# Mako_DSP_USBR1_1.net
KiCad netlist of a schematic drawn in Altium Designer
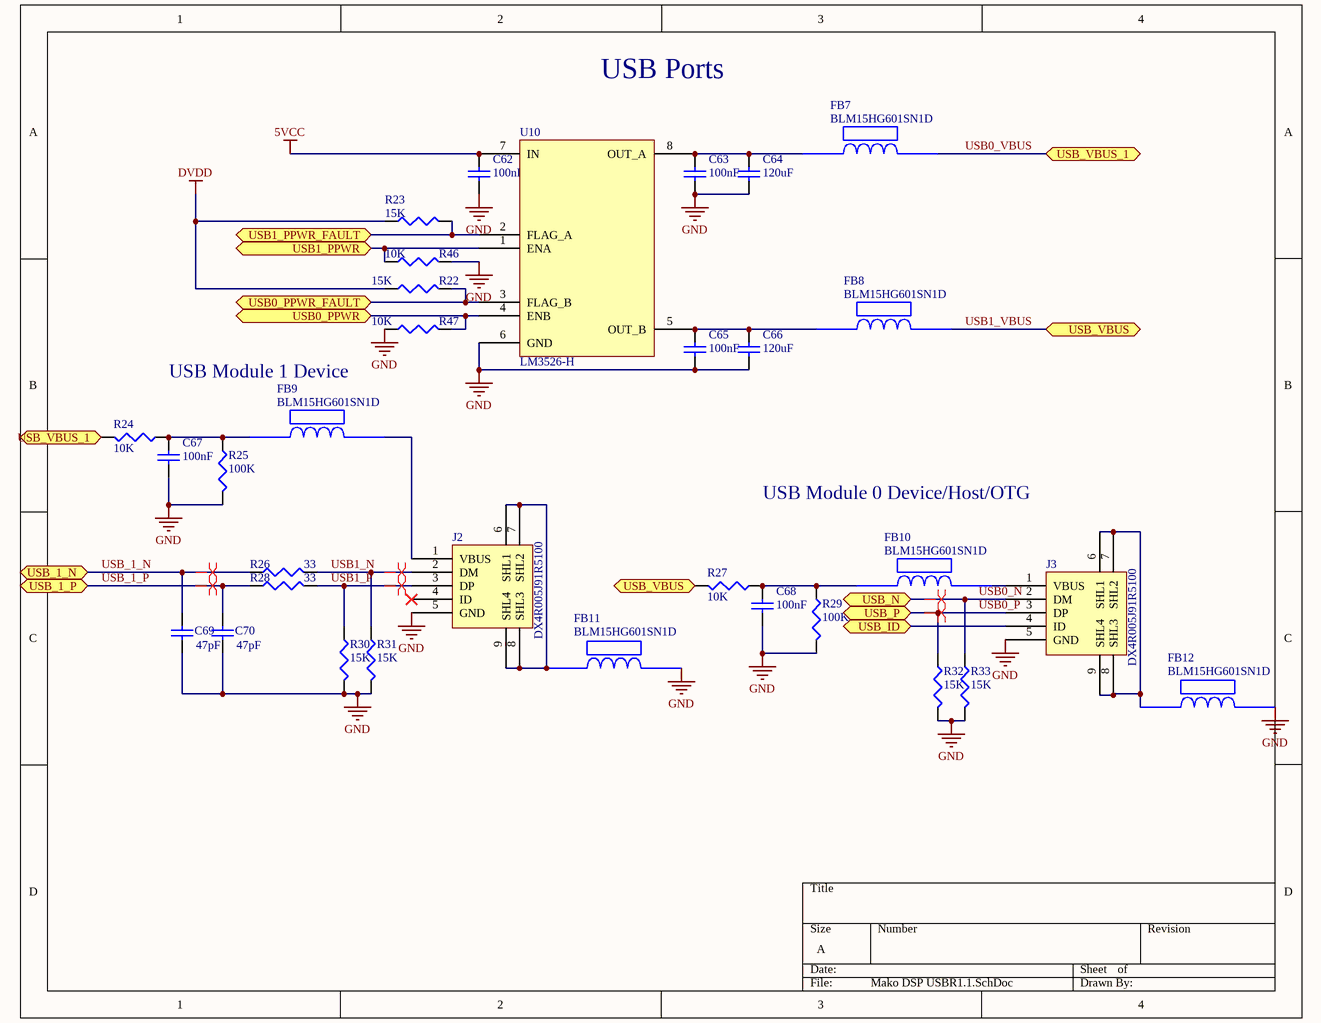
[diagram p0: Mako DSP USBR1.1.SchDoc]

(export (version "E")
  (design (tool "Eeschema 10.0.6"))
  (components
    (comp (ref "C62")
      (value "100nF")
      (footprint "1608[0603]")
      (description "Capacitor (Semiconductor SIM Model)")
      (fields (field (name "Comment") "Cap Semi") (field (name "PUBLISHER") "Altium Limited"))
      (libsource (lib "Miscellaneous Devices") (part "Cap Semi"))
    )
    (comp (ref "C63")
      (value "100nF")
      (footprint "1608[0603]")
      (description "Capacitor (Semiconductor SIM Model)")
      (fields (field (name "Comment") "Cap Semi") (field (name "PUBLISHER") "Altium Limited"))
      (libsource (lib "Miscellaneous Devices") (part "Cap Semi"))
    )
    (comp (ref "C64")
      (value "120uF")
      (footprint "1608[0603]")
      (description "Capacitor (Semiconductor SIM Model)")
      (fields (field (name "Comment") "Cap Semi") (field (name "PUBLISHER") "Altium Limited"))
      (libsource (lib "Miscellaneous Devices") (part "Cap Semi"))
    )
    (comp (ref "C65")
      (value "100nF")
      (footprint "1608[0603]")
      (description "Capacitor (Semiconductor SIM Model)")
      (fields (field (name "Comment") "Cap Semi") (field (name "PUBLISHER") "Altium Limited"))
      (libsource (lib "Miscellaneous Devices") (part "Cap Semi"))
    )
    (comp (ref "C66")
      (value "120uF")
      (footprint "1608[0603]")
      (description "Capacitor (Semiconductor SIM Model)")
      (fields (field (name "Comment") "Cap Semi") (field (name "PUBLISHER") "Altium Limited"))
      (libsource (lib "Miscellaneous Devices") (part "Cap Semi"))
    )
    (comp (ref "C67")
      (value "100nF")
      (footprint "1608[0603]")
      (description "Capacitor (Semiconductor SIM Model)")
      (fields (field (name "Comment") "Cap Semi") (field (name "PUBLISHER") "Altium Limited"))
      (libsource (lib "Miscellaneous Devices") (part "Cap Semi"))
    )
    (comp (ref "C68")
      (value "100nF")
      (footprint "1608[0603]")
      (description "Capacitor (Semiconductor SIM Model)")
      (fields (field (name "Comment") "Cap Semi") (field (name "PUBLISHER") "Altium Limited"))
      (libsource (lib "Miscellaneous Devices") (part "Cap Semi"))
    )
    (comp (ref "C69")
      (value "47pF")
      (footprint "1608[0603]")
      (description "Capacitor (Semiconductor SIM Model)")
      (fields (field (name "Comment") "Cap Semi") (field (name "PUBLISHER") "Altium Limited"))
      (libsource (lib "Miscellaneous Devices") (part "Cap Semi"))
    )
    (comp (ref "C70")
      (value "47pF")
      (footprint "1608[0603]")
      (description "Capacitor (Semiconductor SIM Model)")
      (fields (field (name "Comment") "Cap Semi") (field (name "PUBLISHER") "Altium Limited"))
      (libsource (lib "Miscellaneous Devices") (part "Cap Semi"))
    )
    (comp (ref "FB7")
      (value "BLM15HG601SN1D")
      (footprint "BLM18PG121SN1D")
      (libsource (lib "AHD Part Library") (part "BLM15HG601SN1D"))
    )
    (comp (ref "FB8")
      (value "BLM15HG601SN1D")
      (footprint "BLM18PG121SN1D")
      (libsource (lib "AHD Part Library") (part "BLM15HG601SN1D"))
    )
    (comp (ref "FB9")
      (value "BLM15HG601SN1D")
      (footprint "BLM18PG121SN1D")
      (libsource (lib "AHD Part Library") (part "BLM15HG601SN1D"))
    )
    (comp (ref "FB10")
      (value "BLM15HG601SN1D")
      (footprint "BLM18PG121SN1D")
      (libsource (lib "AHD Part Library") (part "BLM15HG601SN1D"))
    )
    (comp (ref "FB11")
      (value "BLM15HG601SN1D")
      (footprint "BLM18PG121SN1D")
      (libsource (lib "AHD Part Library") (part "BLM15HG601SN1D"))
    )
    (comp (ref "FB12")
      (value "BLM15HG601SN1D")
      (footprint "BLM18PG121SN1D")
      (libsource (lib "AHD Part Library") (part "BLM15HG601SN1D"))
    )
    (comp (ref "J2")
      (value "DX4R005J91R5100")
      (footprint "Micro USB Circular Holes Only")
      (description "Micro USB Jack B")
      (libsource (lib "Adams Altium Library") (part "Micro USB"))
    )
    (comp (ref "J3")
      (value "DX4R005J91R5100")
      (footprint "Micro USB Circular Holes Only")
      (description "Micro USB Jack B")
      (libsource (lib "Adams Altium Library") (part "Micro USB"))
    )
    (comp (ref "R22")
      (value "15K")
      (footprint "J1-0603")
      (description "Resistor")
      (fields (field (name "Comment") "Res3") (field (name "PUBLISHER") "Altium Limited"))
      (libsource (lib "Miscellaneous Devices") (part "Res3"))
    )
    (comp (ref "R23")
      (value "15K")
      (footprint "J1-0603")
      (description "Resistor")
      (fields (field (name "Comment") "Res3") (field (name "PUBLISHER") "Altium Limited"))
      (libsource (lib "Miscellaneous Devices") (part "Res3"))
    )
    (comp (ref "R24")
      (value "10K")
      (footprint "J1-0603")
      (description "Resistor")
      (fields (field (name "Comment") "Res3") (field (name "PUBLISHER") "Altium Limited"))
      (libsource (lib "Miscellaneous Devices") (part "Res3"))
    )
    (comp (ref "R25")
      (value "100K")
      (footprint "J1-0603")
      (description "Resistor")
      (fields (field (name "Comment") "Res3") (field (name "PUBLISHER") "Altium Limited"))
      (libsource (lib "Miscellaneous Devices") (part "Res3"))
    )
    (comp (ref "R26")
      (value "33")
      (footprint "J1-0603")
      (description "Resistor")
      (fields (field (name "Comment") "Res3") (field (name "PUBLISHER") "Altium Limited"))
      (libsource (lib "Miscellaneous Devices") (part "Res3"))
    )
    (comp (ref "R27")
      (value "10K")
      (footprint "J1-0603")
      (description "Resistor")
      (fields (field (name "Comment") "Res3") (field (name "PUBLISHER") "Altium Limited"))
      (libsource (lib "Miscellaneous Devices") (part "Res3"))
    )
    (comp (ref "R28")
      (value "33")
      (footprint "J1-0603")
      (description "Resistor")
      (fields (field (name "Comment") "Res3") (field (name "PUBLISHER") "Altium Limited"))
      (libsource (lib "Miscellaneous Devices") (part "Res3"))
    )
    (comp (ref "R29")
      (value "100K")
      (footprint "J1-0603")
      (description "Resistor")
      (fields (field (name "Comment") "Res3") (field (name "PUBLISHER") "Altium Limited"))
      (libsource (lib "Miscellaneous Devices") (part "Res3"))
    )
    (comp (ref "R30")
      (value "15K")
      (footprint "J1-0603")
      (description "Resistor")
      (fields (field (name "Comment") "Res3") (field (name "PUBLISHER") "Altium Limited"))
      (libsource (lib "Miscellaneous Devices") (part "Res3"))
    )
    (comp (ref "R31")
      (value "15K")
      (footprint "J1-0603")
      (description "Resistor")
      (fields (field (name "Comment") "Res3") (field (name "PUBLISHER") "Altium Limited"))
      (libsource (lib "Miscellaneous Devices") (part "Res3"))
    )
    (comp (ref "R32")
      (value "15K")
      (footprint "J1-0603")
      (description "Resistor")
      (fields (field (name "Comment") "Res3") (field (name "PUBLISHER") "Altium Limited"))
      (libsource (lib "Miscellaneous Devices") (part "Res3"))
    )
    (comp (ref "R33")
      (value "15K")
      (footprint "J1-0603")
      (description "Resistor")
      (fields (field (name "Comment") "Res3") (field (name "PUBLISHER") "Altium Limited"))
      (libsource (lib "Miscellaneous Devices") (part "Res3"))
    )
    (comp (ref "R46")
      (value "10K")
      (footprint "J1-0603")
      (description "Resistor")
      (fields (field (name "Comment") "Res3") (field (name "PUBLISHER") "Altium Limited"))
      (libsource (lib "Miscellaneous Devices") (part "Res3"))
    )
    (comp (ref "R47")
      (value "10K")
      (footprint "J1-0603")
      (description "Resistor")
      (fields (field (name "Comment") "Res3") (field (name "PUBLISHER") "Altium Limited"))
      (libsource (lib "Miscellaneous Devices") (part "Res3"))
    )
    (comp (ref "U10")
      (value "LM3526-H")
      (footprint "LM3526")
      (libsource (lib "Adams Altium Library") (part "LM3526"))
    )
  )
  (nets
    (net (code "1") (name "/USB0_N") (class "Default")
      (node (ref "J3") (pin "2") (pinfunction "DM_2") (pintype "passive"))
      (node (ref "R33") (pin "1") (pinfunction "1_1") (pintype "passive"))
    )
    (net (code "2") (name "/USB0_P") (class "Default")
      (node (ref "J3") (pin "3") (pinfunction "DP_3") (pintype "passive"))
      (node (ref "R32") (pin "1") (pinfunction "1_1") (pintype "passive"))
    )
    (net (code "3") (name "/USB0_PPWR") (class "Default")
      (node (ref "R47") (pin "2") (pinfunction "2_2") (pintype "passive"))
      (node (ref "U10") (pin "4") (pinfunction "ENB_4") (pintype "passive"))
    )
    (net (code "4") (name "/USB0_PPWR_FAULT") (class "Default")
      (node (ref "R22") (pin "2") (pinfunction "2_2") (pintype "passive"))
      (node (ref "U10") (pin "3") (pinfunction "FLAG_B_3") (pintype "passive"))
    )
    (net (code "5") (name "/USB0_VBUS") (class "Default")
      (node (ref "FB7") (pin "2") (pinfunction "2_2") (pintype "passive"))
      (node (ref "R24") (pin "2") (pinfunction "2_2") (pintype "passive"))
    )
    (net (code "6") (name "/USB1_N") (class "Default")
      (node (ref "J2") (pin "2") (pinfunction "DM_2") (pintype "passive"))
      (node (ref "R26") (pin "2") (pinfunction "2_2") (pintype "passive"))
      (node (ref "R31") (pin "1") (pinfunction "1_1") (pintype "passive"))
    )
    (net (code "7") (name "/USB1_P") (class "Default")
      (node (ref "J2") (pin "3") (pinfunction "DP_3") (pintype "passive"))
      (node (ref "R28") (pin "2") (pinfunction "2_2") (pintype "passive"))
      (node (ref "R30") (pin "1") (pinfunction "1_1") (pintype "passive"))
    )
    (net (code "8") (name "/USB1_PPWR") (class "Default")
      (node (ref "R46") (pin "1") (pinfunction "1_1") (pintype "passive"))
      (node (ref "U10") (pin "1") (pinfunction "ENA_1") (pintype "passive"))
    )
    (net (code "9") (name "/USB1_PPWR_FAULT") (class "Default")
      (node (ref "R23") (pin "2") (pinfunction "2_2") (pintype "passive"))
      (node (ref "U10") (pin "2") (pinfunction "FLAG_A_2") (pintype "passive"))
    )
    (net (code "10") (name "/USB1_VBUS") (class "Default")
      (node (ref "FB8") (pin "2") (pinfunction "2_2") (pintype "passive"))
      (node (ref "R27") (pin "2") (pinfunction "2_2") (pintype "passive"))
    )
    (net (code "11") (name "/USB_1_N") (class "Default")
      (node (ref "C69") (pin "2") (pinfunction "2_2") (pintype "passive"))
      (node (ref "R26") (pin "1") (pinfunction "1_1") (pintype "passive"))
    )
    (net (code "12") (name "/USB_1_P") (class "Default")
      (node (ref "C70") (pin "2") (pinfunction "2_2") (pintype "passive"))
      (node (ref "R28") (pin "1") (pinfunction "1_1") (pintype "passive"))
    )
    (net (code "13") (name "/USB_ID") (class "Default")
      (node (ref "J3") (pin "4") (pinfunction "ID_4") (pintype "passive"))
    )
    (net (code "14") (name "5VCC") (class "Default")
      (node (ref "C62") (pin "2") (pinfunction "2_2") (pintype "passive"))
      (node (ref "U10") (pin "7") (pinfunction "IN_7") (pintype "passive"))
    )
    (net (code "15") (name "DVDD") (class "Default")
      (node (ref "R22") (pin "1") (pinfunction "1_1") (pintype "passive"))
      (node (ref "R23") (pin "1") (pinfunction "1_1") (pintype "passive"))
    )
    (net (code "16") (name "GND") (class "Default")
      (node (ref "C62") (pin "1") (pinfunction "1_1") (pintype "passive"))
      (node (ref "C63") (pin "1") (pinfunction "1_1") (pintype "passive"))
      (node (ref "C64") (pin "1") (pinfunction "1_1") (pintype "passive"))
      (node (ref "C65") (pin "1") (pinfunction "1_1") (pintype "passive"))
      (node (ref "C66") (pin "1") (pinfunction "1_1") (pintype "passive"))
      (node (ref "C67") (pin "1") (pinfunction "1_1") (pintype "passive"))
      (node (ref "C68") (pin "1") (pinfunction "1_1") (pintype "passive"))
      (node (ref "C69") (pin "1") (pinfunction "1_1") (pintype "passive"))
      (node (ref "C70") (pin "1") (pinfunction "1_1") (pintype "passive"))
      (node (ref "FB11") (pin "2") (pinfunction "2_2") (pintype "passive"))
      (node (ref "FB12") (pin "2") (pinfunction "2_2") (pintype "passive"))
      (node (ref "J2") (pin "5") (pinfunction "GND_5") (pintype "passive"))
      (node (ref "J3") (pin "5") (pinfunction "GND_5") (pintype "passive"))
      (node (ref "R25") (pin "2") (pinfunction "2_2") (pintype "passive"))
      (node (ref "R29") (pin "2") (pinfunction "2_2") (pintype "passive"))
      (node (ref "R30") (pin "2") (pinfunction "2_2") (pintype "passive"))
      (node (ref "R31") (pin "2") (pinfunction "2_2") (pintype "passive"))
      (node (ref "R32") (pin "2") (pinfunction "2_2") (pintype "passive"))
      (node (ref "R33") (pin "2") (pinfunction "2_2") (pintype "passive"))
      (node (ref "R46") (pin "2") (pinfunction "2_2") (pintype "passive"))
      (node (ref "R47") (pin "1") (pinfunction "1_1") (pintype "passive"))
      (node (ref "U10") (pin "6") (pinfunction "GND_6") (pintype "passive"))
    )
    (net (code "17") (name "Net-(C67-Pad2)") (class "Default")
      (node (ref "C67") (pin "2") (pinfunction "2_2") (pintype "passive"))
      (node (ref "FB9") (pin "1") (pinfunction "1_1") (pintype "passive"))
      (node (ref "R24") (pin "1") (pinfunction "1_1") (pintype "passive"))
      (node (ref "R25") (pin "1") (pinfunction "1_1") (pintype "passive"))
    )
    (net (code "18") (name "Net-(C68-Pad2)") (class "Default")
      (node (ref "C68") (pin "2") (pinfunction "2_2") (pintype "passive"))
      (node (ref "FB10") (pin "1") (pinfunction "1_1") (pintype "passive"))
      (node (ref "R27") (pin "1") (pinfunction "1_1") (pintype "passive"))
      (node (ref "R29") (pin "1") (pinfunction "1_1") (pintype "passive"))
    )
    (net (code "19") (name "Net-(J2-SHL1)") (class "Default")
      (node (ref "FB11") (pin "1") (pinfunction "1_1") (pintype "passive"))
      (node (ref "J2") (pin "6") (pinfunction "SHL1_6") (pintype "passive"))
      (node (ref "J2") (pin "7") (pinfunction "SHL2_7") (pintype "passive"))
      (node (ref "J2") (pin "8") (pinfunction "SHL3_8") (pintype "passive"))
      (node (ref "J2") (pin "9") (pinfunction "SHL4_9") (pintype "passive"))
    )
    (net (code "20") (name "Net-(J2-VBUS)") (class "Default")
      (node (ref "FB9") (pin "2") (pinfunction "2_2") (pintype "passive"))
      (node (ref "J2") (pin "1") (pinfunction "VBUS_1") (pintype "passive"))
    )
    (net (code "21") (name "Net-(J3-SHL1)") (class "Default")
      (node (ref "FB12") (pin "1") (pinfunction "1_1") (pintype "passive"))
      (node (ref "J3") (pin "6") (pinfunction "SHL1_6") (pintype "passive"))
      (node (ref "J3") (pin "7") (pinfunction "SHL2_7") (pintype "passive"))
      (node (ref "J3") (pin "8") (pinfunction "SHL3_8") (pintype "passive"))
      (node (ref "J3") (pin "9") (pinfunction "SHL4_9") (pintype "passive"))
    )
    (net (code "22") (name "Net-(J3-VBUS)") (class "Default")
      (node (ref "FB10") (pin "2") (pinfunction "2_2") (pintype "passive"))
      (node (ref "J3") (pin "1") (pinfunction "VBUS_1") (pintype "passive"))
    )
    (net (code "23") (name "Net-(U10-OUT_A)") (class "Default")
      (node (ref "C63") (pin "2") (pinfunction "2_2") (pintype "passive"))
      (node (ref "C64") (pin "2") (pinfunction "2_2") (pintype "passive"))
      (node (ref "FB7") (pin "1") (pinfunction "1_1") (pintype "passive"))
      (node (ref "U10") (pin "8") (pinfunction "OUT_A_8") (pintype "passive"))
    )
    (net (code "24") (name "Net-(U10-OUT_B)") (class "Default")
      (node (ref "C65") (pin "2") (pinfunction "2_2") (pintype "passive"))
      (node (ref "C66") (pin "2") (pinfunction "2_2") (pintype "passive"))
      (node (ref "FB8") (pin "1") (pinfunction "1_1") (pintype "passive"))
      (node (ref "U10") (pin "5") (pinfunction "OUT_B_5") (pintype "passive"))
    )
    (net (code "25") (name "unconnected-(J2-ID-Pad4)") (class "Default")
      (node (ref "J2") (pin "4") (pinfunction "ID_4") (pintype "passive+no_connect"))
    )
  )
)
